# MCU.net
KiCad netlist of a schematic drawn in Altium Designer
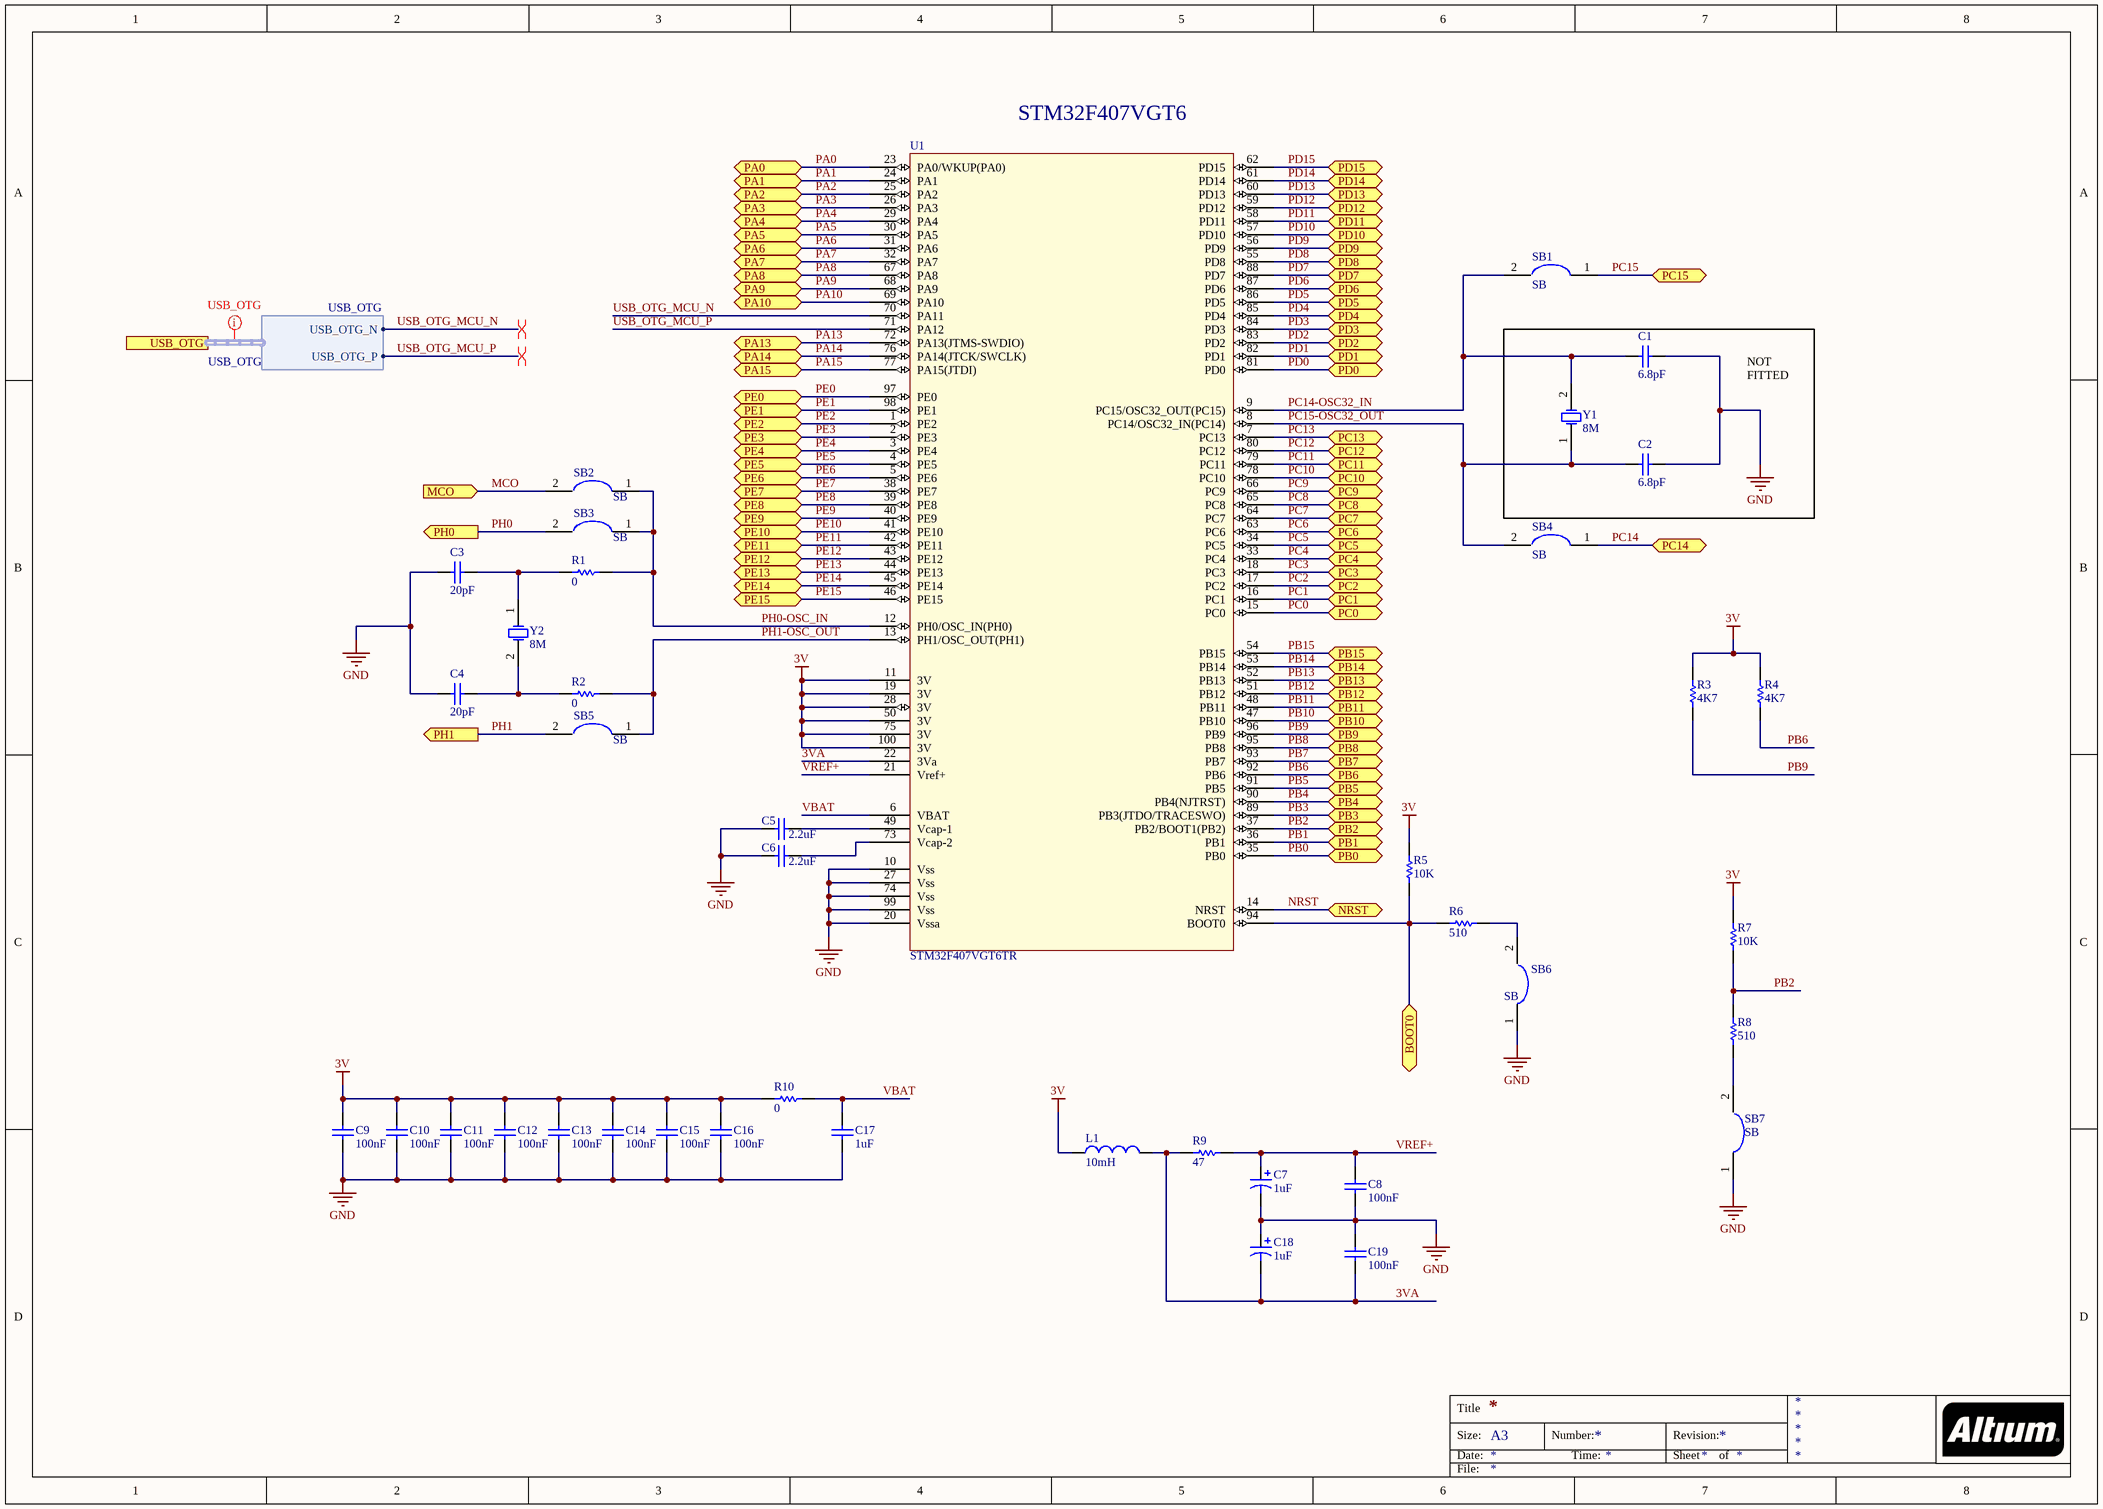
[diagram p0: MCU.SchDoc]

(export (version "E")
  (design (tool "Eeschema 10.0.6"))
  (components
    (comp (ref "C1")
      (value "6.8pF")
      (footprint "CAPC0603B")
      (description "Capacitor")
      (fields (field (name "Comment") "Cap") (field (name "PUBLISHER") "Altium Limited"))
      (libsource (lib "STM32F4DISCOVERY") (part "Cap_1"))
    )
    (comp (ref "C2")
      (value "6.8pF")
      (footprint "CAPC0603B")
      (description "Capacitor")
      (fields (field (name "Comment") "Cap") (field (name "PUBLISHER") "Altium Limited"))
      (libsource (lib "STM32F4DISCOVERY") (part "Cap_1"))
    )
    (comp (ref "C3")
      (value "20pF")
      (footprint "CAPC0603B")
      (description "Capacitor")
      (fields (field (name "Comment") "Cap") (field (name "PUBLISHER") "Altium Limited"))
      (libsource (lib "STM32F4DISCOVERY") (part "Cap"))
    )
    (comp (ref "C4")
      (value "20pF")
      (footprint "CAPC0603B")
      (description "Capacitor")
      (fields (field (name "Comment") "Cap") (field (name "PUBLISHER") "Altium Limited"))
      (libsource (lib "STM32F4DISCOVERY") (part "Cap"))
    )
    (comp (ref "C5")
      (value "2.2uF")
      (footprint "CAPC0603B")
      (description "Capacitor")
      (fields (field (name "Comment") "Cap") (field (name "PUBLISHER") "Altium Limited"))
      (libsource (lib "STM32F4DISCOVERY") (part "Cap_2"))
    )
    (comp (ref "C6")
      (value "2.2uF")
      (footprint "CAPC0603B")
      (description "Capacitor")
      (fields (field (name "Comment") "Cap") (field (name "PUBLISHER") "Altium Limited"))
      (libsource (lib "STM32F4DISCOVERY") (part "Cap_2"))
    )
    (comp (ref "C7")
      (value "1uF")
      (footprint "TANTALUM CASE A_LEVEL B")
      (description "Polarized Capacitor (Radial)")
      (fields (field (name "Comment") "Cap Pol1") (field (name "PUBLISHER") "Altium Limited"))
      (libsource (lib "STM32F4DISCOVERY") (part "Cap Pol1"))
    )
    (comp (ref "C8")
      (value "100nF")
      (footprint "CAPC0603B")
      (description "Capacitor")
      (fields (field (name "Comment") "Cap") (field (name "PUBLISHER") "Altium Limited"))
      (libsource (lib "STM32F4DISCOVERY") (part "Cap_3"))
    )
    (comp (ref "C9")
      (value "100nF")
      (footprint "CAPC0603B")
      (description "Capacitor")
      (fields (field (name "Comment") "Cap") (field (name "PUBLISHER") "Altium Limited"))
      (libsource (lib "STM32F4DISCOVERY") (part "Cap_3"))
    )
    (comp (ref "C10")
      (value "100nF")
      (footprint "CAPC0603B")
      (description "Capacitor")
      (fields (field (name "Comment") "Cap") (field (name "PUBLISHER") "Altium Limited"))
      (libsource (lib "STM32F4DISCOVERY") (part "Cap_3"))
    )
    (comp (ref "C11")
      (value "100nF")
      (footprint "CAPC0603B")
      (description "Capacitor")
      (fields (field (name "Comment") "Cap") (field (name "PUBLISHER") "Altium Limited"))
      (libsource (lib "STM32F4DISCOVERY") (part "Cap_3"))
    )
    (comp (ref "C12")
      (value "100nF")
      (footprint "CAPC0603B")
      (description "Capacitor")
      (fields (field (name "Comment") "Cap") (field (name "PUBLISHER") "Altium Limited"))
      (libsource (lib "STM32F4DISCOVERY") (part "Cap_3"))
    )
    (comp (ref "C13")
      (value "100nF")
      (footprint "CAPC0603B")
      (description "Capacitor")
      (fields (field (name "Comment") "Cap") (field (name "PUBLISHER") "Altium Limited"))
      (libsource (lib "STM32F4DISCOVERY") (part "Cap_3"))
    )
    (comp (ref "C14")
      (value "100nF")
      (footprint "CAPC0603B")
      (description "Capacitor")
      (fields (field (name "Comment") "Cap") (field (name "PUBLISHER") "Altium Limited"))
      (libsource (lib "STM32F4DISCOVERY") (part "Cap_3"))
    )
    (comp (ref "C15")
      (value "100nF")
      (footprint "CAPC0603B")
      (description "Capacitor")
      (fields (field (name "Comment") "Cap") (field (name "PUBLISHER") "Altium Limited"))
      (libsource (lib "STM32F4DISCOVERY") (part "Cap_3"))
    )
    (comp (ref "C16")
      (value "100nF")
      (footprint "CAPC0603B")
      (description "Capacitor")
      (fields (field (name "Comment") "Cap") (field (name "PUBLISHER") "Altium Limited"))
      (libsource (lib "STM32F4DISCOVERY") (part "Cap_3"))
    )
    (comp (ref "C17")
      (value "1uF")
      (footprint "CAPC0603B")
      (description "Capacitor")
      (fields (field (name "Comment") "Cap") (field (name "PUBLISHER") "Altium Limited"))
      (libsource (lib "STM32F4DISCOVERY") (part "Cap_4"))
    )
    (comp (ref "C18")
      (value "1uF")
      (footprint "TANTALUM CASE A_LEVEL B")
      (description "Polarized Capacitor (Radial)")
      (fields (field (name "Comment") "Cap Pol1") (field (name "PUBLISHER") "Altium Limited"))
      (libsource (lib "STM32F4DISCOVERY") (part "Cap Pol1"))
    )
    (comp (ref "C19")
      (value "100nF")
      (footprint "CAPC0603B")
      (description "Capacitor")
      (fields (field (name "Comment") "Cap") (field (name "PUBLISHER") "Altium Limited"))
      (libsource (lib "STM32F4DISCOVERY") (part "Cap_3"))
    )
    (comp (ref "L1")
      (value "10mH")
      (footprint "0402-A")
      (description "Inductor")
      (fields (field (name "PUBLISHER") "Altium Limited"))
      (libsource (lib "STM32F4DISCOVERY") (part "Inductor"))
    )
    (comp (ref "R1")
      (value "0")
      (footprint "RESC0603B")
      (description "Resistor")
      (fields (field (name "Comment") "Res1") (field (name "PUBLISHER") "Altium Limited"))
      (libsource (lib "STM32F4DISCOVERY") (part "Res1"))
    )
    (comp (ref "R2")
      (value "0")
      (footprint "RESC0603B")
      (description "Resistor")
      (fields (field (name "Comment") "Res1") (field (name "PUBLISHER") "Altium Limited"))
      (libsource (lib "STM32F4DISCOVERY") (part "Res1"))
    )
    (comp (ref "R3")
      (value "4K7")
      (footprint "RESC0402B")
      (description "Resistor")
      (fields (field (name "Comment") "Res1") (field (name "PUBLISHER") "Altium Limited"))
      (libsource (lib "STM32F4DISCOVERY") (part "Res1_16"))
    )
    (comp (ref "R4")
      (value "4K7")
      (footprint "RESC0402B")
      (description "Resistor")
      (fields (field (name "Comment") "Res1") (field (name "PUBLISHER") "Altium Limited"))
      (libsource (lib "STM32F4DISCOVERY") (part "Res1_16"))
    )
    (comp (ref "R5")
      (value "10K")
      (footprint "RESC0603B")
      (description "Resistor")
      (fields (field (name "Comment") "Res1") (field (name "PUBLISHER") "Altium Limited"))
      (libsource (lib "STM32F4DISCOVERY") (part "Res1_2"))
    )
    (comp (ref "R6")
      (value "510")
      (footprint "RESC0603B")
      (description "Resistor")
      (fields (field (name "Comment") "Res1") (field (name "PUBLISHER") "Altium Limited"))
      (libsource (lib "STM32F4DISCOVERY") (part "Res1_1"))
    )
    (comp (ref "R7")
      (value "10K")
      (footprint "RESC0603B")
      (description "Resistor")
      (fields (field (name "Comment") "Res1") (field (name "PUBLISHER") "Altium Limited"))
      (libsource (lib "STM32F4DISCOVERY") (part "Res1_2"))
    )
    (comp (ref "R8")
      (value "510")
      (footprint "RESC0603B")
      (description "Resistor")
      (fields (field (name "Comment") "Res1") (field (name "PUBLISHER") "Altium Limited"))
      (libsource (lib "STM32F4DISCOVERY") (part "Res1_1"))
    )
    (comp (ref "R9")
      (value "47")
      (footprint "RESC0603B")
      (description "Resistor")
      (fields (field (name "Comment") "Res1") (field (name "PUBLISHER") "Altium Limited"))
      (libsource (lib "STM32F4DISCOVERY") (part "Res1_3"))
    )
    (comp (ref "R10")
      (value "0")
      (footprint "RESC0603B")
      (description "Resistor")
      (fields (field (name "Comment") "Res1") (field (name "PUBLISHER") "Altium Limited"))
      (libsource (lib "STM32F4DISCOVERY") (part "Res1"))
    )
    (comp (ref "SB1") (value "SB") (footprint "SB") (libsource (lib "STM32F4DISCOVERY") (part "SB")))
    (comp (ref "SB2") (value "SB") (footprint "SB") (libsource (lib "STM32F4DISCOVERY") (part "SB")))
    (comp (ref "SB3") (value "SB") (footprint "SB") (libsource (lib "STM32F4DISCOVERY") (part "SB")))
    (comp (ref "SB4") (value "SB") (footprint "SB") (libsource (lib "STM32F4DISCOVERY") (part "SB")))
    (comp (ref "SB5") (value "SB") (footprint "SB") (libsource (lib "STM32F4DISCOVERY") (part "SB")))
    (comp (ref "SB6") (value "SB") (footprint "SB") (libsource (lib "") (part "SB_1")))
    (comp (ref "SB7") (value "SB") (footprint "SB") (libsource (lib "") (part "SB_1")))
    (comp (ref "U1")
      (value "STM32F407VGT6TR")
      (footprint "LQFP100B")
      (description "STMICROELECTRONICS - STM32F407VGT6TR - MCU, 32BIT, CORTEX-M4, 168MHZ, LQFP-100")
      (fields (field (name "MANUFACTURER") "STMICROELECTRONICS"))
      (libsource (lib "STM32F4DISCOVERY") (part "STM32F407VGT6TR"))
    )
    (comp (ref "Y1")
      (value "8M")
      (footprint "HC-49S")
      (description "Crystal Oscillator")
      (fields (field (name "PUBLISHER") "Altium Limited"))
      (libsource (lib "STM32F4DISCOVERY") (part "XTAL"))
    )
    (comp (ref "Y2")
      (value "8M")
      (footprint "HC-49S")
      (description "Crystal Oscillator")
      (fields (field (name "PUBLISHER") "Altium Limited"))
      (libsource (lib "STM32F4DISCOVERY") (part "XTAL"))
    )
  )
  (nets
    (net (code "2") (name "/3VA") (class "Default")
      (node (ref "C18") (pin "2") (pinfunction "2_2") (pintype "passive"))
      (node (ref "C19") (pin "1") (pinfunction "1_1") (pintype "passive"))
      (node (ref "L1") (pin "2") (pinfunction "2_2") (pintype "passive"))
      (node (ref "R9") (pin "1") (pinfunction "1_1") (pintype "passive"))
      (node (ref "U1") (pin "22") (pinfunction "3Va_22") (pintype "power_in"))
    )
    (net (code "3") (name "/BOOT0") (class "Default")
      (node (ref "R5") (pin "1") (pinfunction "1_1") (pintype "passive"))
      (node (ref "R6") (pin "1") (pinfunction "1_1") (pintype "passive"))
      (node (ref "U1") (pin "94") (pinfunction "BOOT0_94") (pintype "bidirectional"))
    )
    (net (code "4") (name "/MCO") (class "Default")
      (node (ref "SB2") (pin "2") (pinfunction "2_2") (pintype "passive"))
    )
    (net (code "5") (name "/NRST") (class "Default")
      (node (ref "U1") (pin "14") (pinfunction "NRST_14") (pintype "bidirectional"))
    )
    (net (code "6") (name "/PA0") (class "Default")
      (node (ref "U1") (pin "23") (pinfunction "PA0/WKUP(PA0)_23") (pintype "bidirectional"))
    )
    (net (code "7") (name "/PA1") (class "Default")
      (node (ref "U1") (pin "24") (pinfunction "PA1_24") (pintype "bidirectional"))
    )
    (net (code "8") (name "/PA2") (class "Default")
      (node (ref "U1") (pin "25") (pinfunction "PA2_25") (pintype "bidirectional"))
    )
    (net (code "9") (name "/PA3") (class "Default")
      (node (ref "U1") (pin "26") (pinfunction "PA3_26") (pintype "bidirectional"))
    )
    (net (code "10") (name "/PA4") (class "Default")
      (node (ref "U1") (pin "29") (pinfunction "PA4_29") (pintype "bidirectional"))
    )
    (net (code "11") (name "/PA5") (class "Default")
      (node (ref "U1") (pin "30") (pinfunction "PA5_30") (pintype "bidirectional"))
    )
    (net (code "12") (name "/PA6") (class "Default")
      (node (ref "U1") (pin "31") (pinfunction "PA6_31") (pintype "bidirectional"))
    )
    (net (code "13") (name "/PA7") (class "Default")
      (node (ref "U1") (pin "32") (pinfunction "PA7_32") (pintype "bidirectional"))
    )
    (net (code "14") (name "/PA8") (class "Default")
      (node (ref "U1") (pin "67") (pinfunction "PA8_67") (pintype "bidirectional"))
    )
    (net (code "15") (name "/PA9") (class "Default")
      (node (ref "U1") (pin "68") (pinfunction "PA9_68") (pintype "bidirectional"))
    )
    (net (code "16") (name "/PA10") (class "Default")
      (node (ref "U1") (pin "69") (pinfunction "PA10_69") (pintype "bidirectional"))
    )
    (net (code "17") (name "/PA13") (class "Default")
      (node (ref "U1") (pin "72") (pinfunction "PA13(JTMS-SWDIO)_72") (pintype "bidirectional"))
    )
    (net (code "18") (name "/PA14") (class "Default")
      (node (ref "U1") (pin "76") (pinfunction "PA14(JTCK/SWCLK)_76") (pintype "bidirectional"))
    )
    (net (code "19") (name "/PA15") (class "Default")
      (node (ref "U1") (pin "77") (pinfunction "PA15(JTDI)_77") (pintype "bidirectional"))
    )
    (net (code "20") (name "/PB0") (class "Default")
      (node (ref "U1") (pin "35") (pinfunction "PB0_35") (pintype "bidirectional"))
    )
    (net (code "21") (name "/PB1") (class "Default")
      (node (ref "U1") (pin "36") (pinfunction "PB1_36") (pintype "bidirectional"))
    )
    (net (code "22") (name "/PB2") (class "Default")
      (node (ref "R7") (pin "1") (pinfunction "1_1") (pintype "passive"))
      (node (ref "R8") (pin "1") (pinfunction "1_1") (pintype "passive"))
      (node (ref "U1") (pin "37") (pinfunction "PB2/BOOT1(PB2)_37") (pintype "bidirectional"))
    )
    (net (code "23") (name "/PB3") (class "Default")
      (node (ref "U1") (pin "89") (pinfunction "PB3(JTDO/TRACESWO)_89") (pintype "bidirectional"))
    )
    (net (code "24") (name "/PB4") (class "Default")
      (node (ref "U1") (pin "90") (pinfunction "PB4(NJTRST)_90") (pintype "bidirectional"))
    )
    (net (code "25") (name "/PB5") (class "Default")
      (node (ref "U1") (pin "91") (pinfunction "PB5_91") (pintype "bidirectional"))
    )
    (net (code "26") (name "/PB6") (class "Default")
      (node (ref "R4") (pin "1") (pinfunction "1_1") (pintype "passive"))
      (node (ref "U1") (pin "92") (pinfunction "PB6_92") (pintype "bidirectional"))
    )
    (net (code "27") (name "/PB7") (class "Default")
      (node (ref "U1") (pin "93") (pinfunction "PB7_93") (pintype "bidirectional"))
    )
    (net (code "28") (name "/PB8") (class "Default")
      (node (ref "U1") (pin "95") (pinfunction "PB8_95") (pintype "bidirectional"))
    )
    (net (code "29") (name "/PB9") (class "Default")
      (node (ref "R3") (pin "1") (pinfunction "1_1") (pintype "passive"))
      (node (ref "U1") (pin "96") (pinfunction "PB9_96") (pintype "bidirectional"))
    )
    (net (code "30") (name "/PB10") (class "Default")
      (node (ref "U1") (pin "47") (pinfunction "PB10_47") (pintype "bidirectional"))
    )
    (net (code "31") (name "/PB11") (class "Default")
      (node (ref "U1") (pin "48") (pinfunction "PB11_48") (pintype "bidirectional"))
    )
    (net (code "32") (name "/PB12") (class "Default")
      (node (ref "U1") (pin "51") (pinfunction "PB12_51") (pintype "bidirectional"))
    )
    (net (code "33") (name "/PB13") (class "Default")
      (node (ref "U1") (pin "52") (pinfunction "PB13_52") (pintype "bidirectional"))
    )
    (net (code "34") (name "/PB14") (class "Default")
      (node (ref "U1") (pin "53") (pinfunction "PB14_53") (pintype "bidirectional"))
    )
    (net (code "35") (name "/PB15") (class "Default")
      (node (ref "U1") (pin "54") (pinfunction "PB15_54") (pintype "bidirectional"))
    )
    (net (code "36") (name "/PC0") (class "Default")
      (node (ref "U1") (pin "15") (pinfunction "PC0_15") (pintype "bidirectional"))
    )
    (net (code "37") (name "/PC1") (class "Default")
      (node (ref "U1") (pin "16") (pinfunction "PC1_16") (pintype "bidirectional"))
    )
    (net (code "38") (name "/PC2") (class "Default")
      (node (ref "U1") (pin "17") (pinfunction "PC2_17") (pintype "bidirectional"))
    )
    (net (code "39") (name "/PC3") (class "Default")
      (node (ref "U1") (pin "18") (pinfunction "PC3_18") (pintype "bidirectional"))
    )
    (net (code "40") (name "/PC4") (class "Default")
      (node (ref "U1") (pin "33") (pinfunction "PC4_33") (pintype "bidirectional"))
    )
    (net (code "41") (name "/PC5") (class "Default")
      (node (ref "U1") (pin "34") (pinfunction "PC5_34") (pintype "bidirectional"))
    )
    (net (code "42") (name "/PC6") (class "Default")
      (node (ref "U1") (pin "63") (pinfunction "PC6_63") (pintype "bidirectional"))
    )
    (net (code "43") (name "/PC7") (class "Default")
      (node (ref "U1") (pin "64") (pinfunction "PC7_64") (pintype "bidirectional"))
    )
    (net (code "44") (name "/PC8") (class "Default")
      (node (ref "U1") (pin "65") (pinfunction "PC8_65") (pintype "bidirectional"))
    )
    (net (code "45") (name "/PC9") (class "Default")
      (node (ref "U1") (pin "66") (pinfunction "PC9_66") (pintype "bidirectional"))
    )
    (net (code "46") (name "/PC10") (class "Default")
      (node (ref "U1") (pin "78") (pinfunction "PC10_78") (pintype "bidirectional"))
    )
    (net (code "47") (name "/PC11") (class "Default")
      (node (ref "U1") (pin "79") (pinfunction "PC11_79") (pintype "bidirectional"))
    )
    (net (code "48") (name "/PC12") (class "Default")
      (node (ref "U1") (pin "80") (pinfunction "PC12_80") (pintype "bidirectional"))
    )
    (net (code "49") (name "/PC13") (class "Default")
      (node (ref "U1") (pin "7") (pinfunction "PC13_7") (pintype "bidirectional"))
    )
    (net (code "50") (name "/PC14") (class "Default")
      (node (ref "SB4") (pin "1") (pinfunction "1_1") (pintype "passive"))
    )
    (net (code "51") (name "/PC14-OSC32_IN") (class "Default")
      (node (ref "C1") (pin "1") (pinfunction "1_1") (pintype "passive"))
      (node (ref "SB1") (pin "2") (pinfunction "2_2") (pintype "passive"))
      (node (ref "U1") (pin "9") (pinfunction "PC15/OSC32_OUT(PC15)_9") (pintype "bidirectional"))
      (node (ref "Y1") (pin "2") (pinfunction "OSC2_2") (pintype "passive"))
    )
    (net (code "52") (name "/PC15") (class "Default")
      (node (ref "SB1") (pin "1") (pinfunction "1_1") (pintype "passive"))
    )
    (net (code "53") (name "/PC15-OSC32_OUT") (class "Default")
      (node (ref "C2") (pin "1") (pinfunction "1_1") (pintype "passive"))
      (node (ref "SB4") (pin "2") (pinfunction "2_2") (pintype "passive"))
      (node (ref "U1") (pin "8") (pinfunction "PC14/OSC32_IN(PC14)_8") (pintype "bidirectional"))
      (node (ref "Y1") (pin "1") (pinfunction "OSC1_1") (pintype "passive"))
    )
    (net (code "54") (name "/PD0") (class "Default")
      (node (ref "U1") (pin "81") (pinfunction "PD0_81") (pintype "bidirectional"))
    )
    (net (code "55") (name "/PD1") (class "Default")
      (node (ref "U1") (pin "82") (pinfunction "PD1_82") (pintype "bidirectional"))
    )
    (net (code "56") (name "/PD2") (class "Default")
      (node (ref "U1") (pin "83") (pinfunction "PD2_83") (pintype "bidirectional"))
    )
    (net (code "57") (name "/PD3") (class "Default")
      (node (ref "U1") (pin "84") (pinfunction "PD3_84") (pintype "bidirectional"))
    )
    (net (code "58") (name "/PD4") (class "Default")
      (node (ref "U1") (pin "85") (pinfunction "PD4_85") (pintype "bidirectional"))
    )
    (net (code "59") (name "/PD5") (class "Default")
      (node (ref "U1") (pin "86") (pinfunction "PD5_86") (pintype "bidirectional"))
    )
    (net (code "60") (name "/PD6") (class "Default")
      (node (ref "U1") (pin "87") (pinfunction "PD6_87") (pintype "bidirectional"))
    )
    (net (code "61") (name "/PD7") (class "Default")
      (node (ref "U1") (pin "88") (pinfunction "PD7_88") (pintype "bidirectional"))
    )
    (net (code "62") (name "/PD8") (class "Default")
      (node (ref "U1") (pin "55") (pinfunction "PD8_55") (pintype "bidirectional"))
    )
    (net (code "63") (name "/PD9") (class "Default")
      (node (ref "U1") (pin "56") (pinfunction "PD9_56") (pintype "bidirectional"))
    )
    (net (code "64") (name "/PD10") (class "Default")
      (node (ref "U1") (pin "57") (pinfunction "PD10_57") (pintype "bidirectional"))
    )
    (net (code "65") (name "/PD11") (class "Default")
      (node (ref "U1") (pin "58") (pinfunction "PD11_58") (pintype "bidirectional"))
    )
    (net (code "66") (name "/PD12") (class "Default")
      (node (ref "U1") (pin "59") (pinfunction "PD12_59") (pintype "bidirectional"))
    )
    (net (code "67") (name "/PD13") (class "Default")
      (node (ref "U1") (pin "60") (pinfunction "PD13_60") (pintype "bidirectional"))
    )
    (net (code "68") (name "/PD14") (class "Default")
      (node (ref "U1") (pin "61") (pinfunction "PD14_61") (pintype "bidirectional"))
    )
    (net (code "69") (name "/PD15") (class "Default")
      (node (ref "U1") (pin "62") (pinfunction "PD15_62") (pintype "bidirectional"))
    )
    (net (code "70") (name "/PE0") (class "Default")
      (node (ref "U1") (pin "97") (pinfunction "PE0_97") (pintype "bidirectional"))
    )
    (net (code "71") (name "/PE1") (class "Default")
      (node (ref "U1") (pin "98") (pinfunction "PE1_98") (pintype "bidirectional"))
    )
    (net (code "72") (name "/PE2") (class "Default")
      (node (ref "U1") (pin "1") (pinfunction "PE2_1") (pintype "bidirectional"))
    )
    (net (code "73") (name "/PE3") (class "Default")
      (node (ref "U1") (pin "2") (pinfunction "PE3_2") (pintype "bidirectional"))
    )
    (net (code "74") (name "/PE4") (class "Default")
      (node (ref "U1") (pin "3") (pinfunction "PE4_3") (pintype "bidirectional"))
    )
    (net (code "75") (name "/PE5") (class "Default")
      (node (ref "U1") (pin "4") (pinfunction "PE5_4") (pintype "bidirectional"))
    )
    (net (code "76") (name "/PE6") (class "Default")
      (node (ref "U1") (pin "5") (pinfunction "PE6_5") (pintype "bidirectional"))
    )
    (net (code "77") (name "/PE7") (class "Default")
      (node (ref "U1") (pin "38") (pinfunction "PE7_38") (pintype "bidirectional"))
    )
    (net (code "78") (name "/PE8") (class "Default")
      (node (ref "U1") (pin "39") (pinfunction "PE8_39") (pintype "bidirectional"))
    )
    (net (code "79") (name "/PE9") (class "Default")
      (node (ref "U1") (pin "40") (pinfunction "PE9_40") (pintype "bidirectional"))
    )
    (net (code "80") (name "/PE10") (class "Default")
      (node (ref "U1") (pin "41") (pinfunction "PE10_41") (pintype "bidirectional"))
    )
    (net (code "81") (name "/PE11") (class "Default")
      (node (ref "U1") (pin "42") (pinfunction "PE11_42") (pintype "bidirectional"))
    )
    (net (code "82") (name "/PE12") (class "Default")
      (node (ref "U1") (pin "43") (pinfunction "PE12_43") (pintype "bidirectional"))
    )
    (net (code "83") (name "/PE13") (class "Default")
      (node (ref "U1") (pin "44") (pinfunction "PE13_44") (pintype "bidirectional"))
    )
    (net (code "84") (name "/PE14") (class "Default")
      (node (ref "U1") (pin "45") (pinfunction "PE14_45") (pintype "bidirectional"))
    )
    (net (code "85") (name "/PE15") (class "Default")
      (node (ref "U1") (pin "46") (pinfunction "PE15_46") (pintype "bidirectional"))
    )
    (net (code "86") (name "/PH0") (class "Default")
      (node (ref "SB3") (pin "2") (pinfunction "2_2") (pintype "passive"))
    )
    (net (code "87") (name "/PH0-OSC_IN") (class "Default")
      (node (ref "R1") (pin "2") (pinfunction "2_2") (pintype "passive"))
      (node (ref "SB2") (pin "1") (pinfunction "1_1") (pintype "passive"))
      (node (ref "SB3") (pin "1") (pinfunction "1_1") (pintype "passive"))
      (node (ref "U1") (pin "12") (pinfunction "PH0/OSC_IN(PH0)_12") (pintype "bidirectional"))
    )
    (net (code "88") (name "/PH1") (class "Default")
      (node (ref "SB5") (pin "2") (pinfunction "2_2") (pintype "passive"))
    )
    (net (code "89") (name "/PH1-OSC_OUT") (class "Default")
      (node (ref "R2") (pin "2") (pinfunction "2_2") (pintype "passive"))
      (node (ref "SB5") (pin "1") (pinfunction "1_1") (pintype "passive"))
      (node (ref "U1") (pin "13") (pinfunction "PH1/OSC_OUT(PH1)_13") (pintype "bidirectional"))
    )
    (net (code "90") (name "/USB_OTG_MCU_N") (class "Default")
      (node (ref "U1") (pin "70") (pinfunction "PA11_70") (pintype "bidirectional"))
    )
    (net (code "91") (name "/USB_OTG_MCU_P") (class "Default")
      (node (ref "U1") (pin "71") (pinfunction "PA12_71") (pintype "bidirectional"))
    )
    (net (code "92") (name "/VBAT") (class "Default")
      (node (ref "C17") (pin "1") (pinfunction "1_1") (pintype "passive"))
      (node (ref "R10") (pin "2") (pinfunction "2_2") (pintype "passive"))
      (node (ref "U1") (pin "6") (pinfunction "VBAT_6") (pintype "power_in"))
    )
    (net (code "93") (name "/VREF+") (class "Default")
      (node (ref "C7") (pin "1") (pinfunction "1_1") (pintype "passive"))
      (node (ref "C8") (pin "2") (pinfunction "2_2") (pintype "passive"))
      (node (ref "R9") (pin "2") (pinfunction "2_2") (pintype "passive"))
      (node (ref "U1") (pin "21") (pinfunction "Vref+_21") (pintype "power_in"))
    )
    (net (code "95") (name "3V") (class "Default")
      (node (ref "C10") (pin "2") (pinfunction "2_2") (pintype "passive"))
      (node (ref "C11") (pin "2") (pinfunction "2_2") (pintype "passive"))
      (node (ref "C12") (pin "2") (pinfunction "2_2") (pintype "passive"))
      (node (ref "C13") (pin "2") (pinfunction "2_2") (pintype "passive"))
      (node (ref "C14") (pin "2") (pinfunction "2_2") (pintype "passive"))
      (node (ref "C15") (pin "2") (pinfunction "2_2") (pintype "passive"))
      (node (ref "C16") (pin "2") (pinfunction "2_2") (pintype "passive"))
      (node (ref "C9") (pin "2") (pinfunction "2_2") (pintype "passive"))
      (node (ref "L1") (pin "1") (pinfunction "1_1") (pintype "passive"))
      (node (ref "R10") (pin "1") (pinfunction "1_1") (pintype "passive"))
      (node (ref "R3") (pin "2") (pinfunction "2_2") (pintype "passive"))
      (node (ref "R4") (pin "2") (pinfunction "2_2") (pintype "passive"))
      (node (ref "R5") (pin "2") (pinfunction "2_2") (pintype "passive"))
      (node (ref "R7") (pin "2") (pinfunction "2_2") (pintype "passive"))
      (node (ref "U1") (pin "100") (pinfunction "3V_100") (pintype "power_in"))
      (node (ref "U1") (pin "11") (pinfunction "3V_11") (pintype "power_in"))
      (node (ref "U1") (pin "19") (pinfunction "3V_19") (pintype "power_in"))
      (node (ref "U1") (pin "28") (pinfunction "3V_28") (pintype "bidirectional"))
      (node (ref "U1") (pin "50") (pinfunction "3V_50") (pintype "power_in"))
      (node (ref "U1") (pin "75") (pinfunction "3V_75") (pintype "power_in"))
    )
    (net (code "96") (name "GND") (class "Default")
      (node (ref "C1") (pin "2") (pinfunction "2_2") (pintype "passive"))
      (node (ref "C10") (pin "1") (pinfunction "1_1") (pintype "passive"))
      (node (ref "C11") (pin "1") (pinfunction "1_1") (pintype "passive"))
      (node (ref "C12") (pin "1") (pinfunction "1_1") (pintype "passive"))
      (node (ref "C13") (pin "1") (pinfunction "1_1") (pintype "passive"))
      (node (ref "C14") (pin "1") (pinfunction "1_1") (pintype "passive"))
      (node (ref "C15") (pin "1") (pinfunction "1_1") (pintype "passive"))
      (node (ref "C16") (pin "1") (pinfunction "1_1") (pintype "passive"))
      (node (ref "C17") (pin "2") (pinfunction "2_2") (pintype "passive"))
      (node (ref "C18") (pin "1") (pinfunction "1_1") (pintype "passive"))
      (node (ref "C19") (pin "2") (pinfunction "2_2") (pintype "passive"))
      (node (ref "C2") (pin "2") (pinfunction "2_2") (pintype "passive"))
      (node (ref "C3") (pin "1") (pinfunction "1_1") (pintype "passive"))
      (node (ref "C4") (pin "1") (pinfunction "1_1") (pintype "passive"))
      (node (ref "C5") (pin "2") (pinfunction "2_2") (pintype "passive"))
      (node (ref "C6") (pin "2") (pinfunction "2_2") (pintype "passive"))
      (node (ref "C7") (pin "2") (pinfunction "2_2") (pintype "passive"))
      (node (ref "C8") (pin "1") (pinfunction "1_1") (pintype "passive"))
      (node (ref "C9") (pin "1") (pinfunction "1_1") (pintype "passive"))
      (node (ref "SB6") (pin "1") (pinfunction "1_1") (pintype "passive"))
      (node (ref "SB7") (pin "1") (pinfunction "1_1") (pintype "passive"))
      (node (ref "U1") (pin "10") (pinfunction "Vss_10") (pintype "power_in"))
      (node (ref "U1") (pin "20") (pinfunction "Vssa_20") (pintype "power_in"))
      (node (ref "U1") (pin "27") (pinfunction "Vss_27") (pintype "power_in"))
      (node (ref "U1") (pin "74") (pinfunction "Vss_74") (pintype "power_in"))
      (node (ref "U1") (pin "99") (pinfunction "Vss_99") (pintype "power_in"))
    )
    (net (code "97") (name "Net-(R6-Pad2)") (class "Default")
      (node (ref "R6") (pin "2") (pinfunction "2_2") (pintype "passive"))
      (node (ref "SB6") (pin "2") (pinfunction "2_2") (pintype "passive"))
    )
    (net (code "98") (name "Net-(R8-Pad2)") (class "Default")
      (node (ref "R8") (pin "2") (pinfunction "2_2") (pintype "passive"))
      (node (ref "SB7") (pin "2") (pinfunction "2_2") (pintype "passive"))
    )
    (net (code "99") (name "Net-(U1-Vcap-1)") (class "Default")
      (node (ref "C5") (pin "1") (pinfunction "1_1") (pintype "passive"))
      (node (ref "U1") (pin "49") (pinfunction "Vcap-1_49") (pintype "power_in"))
    )
    (net (code "100") (name "Net-(U1-Vcap-2)") (class "Default")
      (node (ref "C6") (pin "1") (pinfunction "1_1") (pintype "passive"))
      (node (ref "U1") (pin "73") (pinfunction "Vcap-2_73") (pintype "power_in"))
    )
    (net (code "101") (name "Net-(Y2-OSC1)") (class "Default")
      (node (ref "C3") (pin "2") (pinfunction "2_2") (pintype "passive"))
      (node (ref "R1") (pin "1") (pinfunction "1_1") (pintype "passive"))
      (node (ref "Y2") (pin "1") (pinfunction "OSC1_1") (pintype "passive"))
    )
    (net (code "102") (name "Net-(Y2-OSC2)") (class "Default")
      (node (ref "C4") (pin "2") (pinfunction "2_2") (pintype "passive"))
      (node (ref "R2") (pin "1") (pinfunction "1_1") (pintype "passive"))
      (node (ref "Y2") (pin "2") (pinfunction "OSC2_2") (pintype "passive"))
    )
  )
)
